# dual_encoder_shield_revB.net
KiCad netlist of a schematic drawn in EAGLE
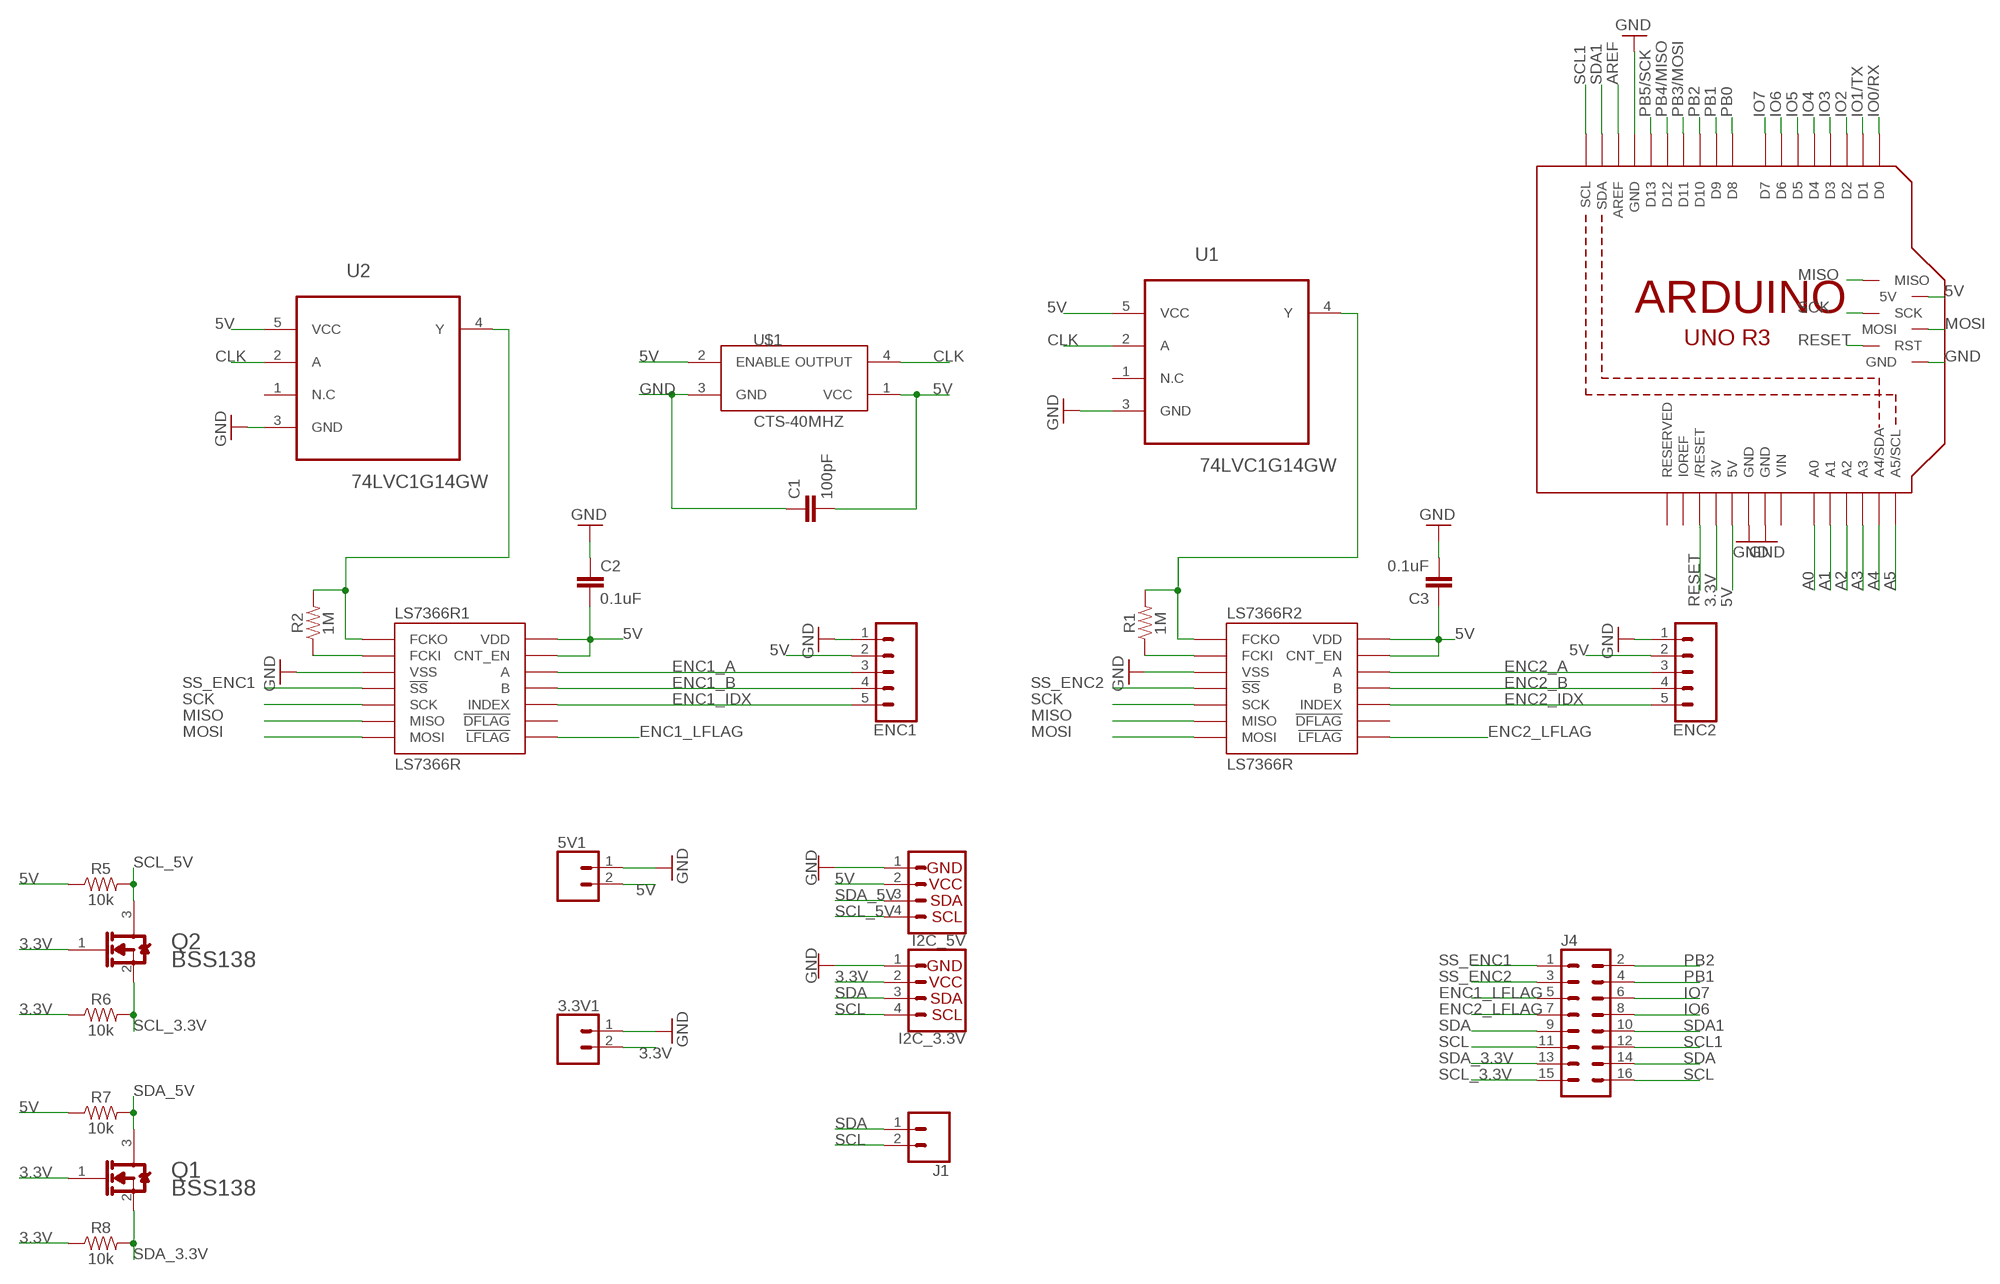
[diagram p0: schematic, sheet 1]

(export (version "E")
  (design (tool "Eeschema 10.0.6"))
  (components
    (comp (ref "3.3V1")
      (value "CONN_02-JST-2MM-SMT")
      (footprint "eagle-import:JST-2-SMD")
      (libsource (lib "eagle-import") (part "CONN_02-JST-2MM-SMT"))
    )
    (comp (ref "5V1")
      (value "CONN_02-JST-2MM-SMT")
      (footprint "eagle-import:JST-2-SMD")
      (libsource (lib "eagle-import") (part "CONN_02-JST-2MM-SMT"))
    )
    (comp (ref "C1")
      (value "100pF")
      (footprint "eagle-import:0603")
      (libsource (lib "eagle-import") (part "100PF-0603-50V-5%"))
    )
    (comp (ref "C2")
      (value "0.1uF")
      (footprint "eagle-import:0603")
      (libsource (lib "eagle-import") (part "0.1UF-0603-25V-5%"))
    )
    (comp (ref "C3")
      (value "0.1uF")
      (footprint "eagle-import:0603")
      (libsource (lib "eagle-import") (part "0.1UF-0603-25V-5%"))
    )
    (comp (ref "ENC1")
      (value "CONN_05")
      (footprint "eagle-import:1X05")
      (libsource (lib "eagle-import") (part "CONN_05"))
    )
    (comp (ref "ENC2")
      (value "CONN_05")
      (footprint "eagle-import:1X05")
      (libsource (lib "eagle-import") (part "CONN_05"))
    )
    (comp (ref "I2C_3.3V")
      (value "QWIIC_CONNECTORJS-1MM")
      (footprint "eagle-import:JST04_1MM_RA")
      (libsource (lib "eagle-import") (part "QWIIC_CONNECTORJS-1MM"))
    )
    (comp (ref "I2C_5V")
      (value "QWIIC_CONNECTORJS-1MM")
      (footprint "eagle-import:JST04_1MM_RA")
      (libsource (lib "eagle-import") (part "QWIIC_CONNECTORJS-1MM"))
    )
    (comp (ref "J1")
      (value "CONN_02")
      (footprint "eagle-import:1X02")
      (libsource (lib "eagle-import") (part "CONN_02"))
    )
    (comp (ref "J4")
      (value "CONN_08X2")
      (footprint "eagle-import:2X8")
      (libsource (lib "eagle-import") (part "CONN_08X2"))
    )
    (comp (ref "LS7366R1")
      (value "LS7366R")
      (footprint "eagle-import:SOIC14")
      (fields (field (name "MF") "LSI"))
      (libsource (lib "eagle-import") (part "LS7366R"))
    )
    (comp (ref "LS7366R2")
      (value "LS7366R")
      (footprint "eagle-import:SOIC14")
      (fields (field (name "MF") "LSI"))
      (libsource (lib "eagle-import") (part "LS7366R"))
    )
    (comp (ref "M1")
      (value "ARDUINO_R3_ICSP")
      (footprint "eagle-import:ARDUINOR3_ICSP")
      (libsource (lib "eagle-import") (part "ARDUINO_R3_ICSP"))
    )
    (comp (ref "Q1")
      (value "ON_SEMI_BSS138ON_SEMI_BSS138_0_0")
      (footprint "eagle-import:ON_SEMI_BSS138_0")
      (fields
        (field (name "DIGIKEY_PART_NUMBER") "BSS138CT-ND")
        (field (name "MF") "ON Semi")
        (field (name "MOUSER_PART_NUMBER") "512-BSS138")
      )
      (libsource (lib "eagle-import") (part "ON_SEMI_BSS138ON_SEMI_BSS138_0_0"))
    )
    (comp (ref "Q2")
      (value "ON_SEMI_BSS138ON_SEMI_BSS138_0_0")
      (footprint "eagle-import:ON_SEMI_BSS138_0")
      (fields
        (field (name "DIGIKEY_PART_NUMBER") "BSS138CT-ND")
        (field (name "MF") "ON Semi")
        (field (name "MOUSER_PART_NUMBER") "512-BSS138")
      )
      (libsource (lib "eagle-import") (part "ON_SEMI_BSS138ON_SEMI_BSS138_0_0"))
    )
    (comp (ref "R1")
      (value "1M")
      (footprint "eagle-import:0603")
      (libsource (lib "eagle-import") (part "1MOHM-0603-1/4W-5%"))
    )
    (comp (ref "R2")
      (value "1M")
      (footprint "eagle-import:0603")
      (libsource (lib "eagle-import") (part "1MOHM-0603-1/4W-5%"))
    )
    (comp (ref "R5")
      (value "10k")
      (footprint "eagle-import:0603")
      (libsource (lib "eagle-import") (part "10KOHM-0603-1/10W-1%"))
    )
    (comp (ref "R6")
      (value "10k")
      (footprint "eagle-import:0603")
      (libsource (lib "eagle-import") (part "10KOHM-0603-1/10W-1%"))
    )
    (comp (ref "R7")
      (value "10k")
      (footprint "eagle-import:0603")
      (libsource (lib "eagle-import") (part "10KOHM-0603-1/10W-1%"))
    )
    (comp (ref "R8")
      (value "10k")
      (footprint "eagle-import:0603")
      (libsource (lib "eagle-import") (part "10KOHM-0603-1/10W-1%"))
    )
    (comp (ref "U$1")
      (value "CTS-40MHZ")
      (footprint "eagle-import:SOIC254P1016X440-4N")
      (libsource (lib "eagle-import") (part "CTS-40MHZ"))
    )
    (comp (ref "U1")
      (value "74LVC1G14GW")
      (footprint "eagle-import:SOT65P210X110-5N")
      (fields (field (name "MF") "NXP Semiconductors"))
      (libsource (lib "eagle-import") (part "74LVC1G14GW"))
    )
    (comp (ref "U2")
      (value "74LVC1G14GW")
      (footprint "eagle-import:SOT65P210X110-5N")
      (fields (field (name "MF") "NXP Semiconductors"))
      (libsource (lib "eagle-import") (part "74LVC1G14GW"))
    )
  )
  (nets
    (net (code "1") (name "/3.3V") (class "Default")
      (node (ref "3.3V1") (pin "2") (pinfunction "1_2") (pintype "passive"))
      (node (ref "I2C_3.3V") (pin "2") (pinfunction "2_2") (pintype "power_in"))
      (node (ref "M1") (pin "3V") (pinfunction "3V_3V") (pintype "power_in"))
      (node (ref "Q1") (pin "1") (pinfunction "G_1") (pintype "bidirectional"))
      (node (ref "Q2") (pin "1") (pinfunction "G_1") (pintype "bidirectional"))
      (node (ref "R6") (pin "1") (pinfunction "1_1") (pintype "passive"))
      (node (ref "R8") (pin "1") (pinfunction "1_1") (pintype "passive"))
    )
    (net (code "2") (name "/5V") (class "Default")
      (node (ref "5V1") (pin "2") (pinfunction "1_2") (pintype "passive"))
      (node (ref "C1") (pin "2") (pinfunction "2_2") (pintype "passive"))
      (node (ref "C2") (pin "2") (pinfunction "2_2") (pintype "passive"))
      (node (ref "C3") (pin "1") (pinfunction "1_1") (pintype "passive"))
      (node (ref "ENC1") (pin "2") (pinfunction "2_2") (pintype "passive"))
      (node (ref "ENC2") (pin "2") (pinfunction "2_2") (pintype "passive"))
      (node (ref "I2C_5V") (pin "2") (pinfunction "2_2") (pintype "power_in"))
      (node (ref "LS7366R1") (pin "13") (pinfunction "CNT_EN_13") (pintype "bidirectional"))
      (node (ref "LS7366R1") (pin "14") (pinfunction "VDD_14") (pintype "bidirectional"))
      (node (ref "LS7366R2") (pin "13") (pinfunction "CNT_EN_13") (pintype "bidirectional"))
      (node (ref "LS7366R2") (pin "14") (pinfunction "VDD_14") (pintype "bidirectional"))
      (node (ref "M1") (pin "5V") (pinfunction "5V_5V") (pintype "power_in"))
      (node (ref "M1") (pin "5V_ICSP") (pinfunction "5V_5V_ICSP") (pintype "passive"))
      (node (ref "R5") (pin "1") (pinfunction "1_1") (pintype "passive"))
      (node (ref "R7") (pin "1") (pinfunction "1_1") (pintype "passive"))
      (node (ref "U$1") (pin "1") (pinfunction "VCC_1") (pintype "bidirectional"))
      (node (ref "U$1") (pin "2") (pinfunction "ENABLE_2") (pintype "bidirectional"))
      (node (ref "U1") (pin "5") (pinfunction "VCC_5") (pintype "power_in"))
      (node (ref "U2") (pin "5") (pinfunction "VCC_5") (pintype "power_in"))
    )
    (net (code "3") (name "/A0") (class "Default")
      (node (ref "M1") (pin "A0") (pinfunction "A0_A0") (pintype "bidirectional"))
    )
    (net (code "4") (name "/A1") (class "Default")
      (node (ref "M1") (pin "A1") (pinfunction "A1_A1") (pintype "bidirectional"))
    )
    (net (code "5") (name "/A2") (class "Default")
      (node (ref "M1") (pin "A2") (pinfunction "A2_A2") (pintype "bidirectional"))
    )
    (net (code "6") (name "/A3") (class "Default")
      (node (ref "M1") (pin "A3") (pinfunction "A3_A3") (pintype "bidirectional"))
    )
    (net (code "7") (name "/A4") (class "Default")
      (node (ref "M1") (pin "A4") (pinfunction "A4/SDA_A4") (pintype "bidirectional"))
    )
    (net (code "8") (name "/A5") (class "Default")
      (node (ref "M1") (pin "A5") (pinfunction "A5/SCL_A5") (pintype "bidirectional"))
    )
    (net (code "9") (name "/AREF") (class "Default")
      (node (ref "M1") (pin "AREF") (pinfunction "AREF_AREF") (pintype "bidirectional"))
    )
    (net (code "10") (name "/CLK") (class "Default")
      (node (ref "U$1") (pin "4") (pinfunction "OUTPUT_4") (pintype "bidirectional"))
      (node (ref "U1") (pin "2") (pinfunction "A_2") (pintype "input"))
      (node (ref "U2") (pin "2") (pinfunction "A_2") (pintype "input"))
    )
    (net (code "11") (name "/ENC1_A") (class "Default")
      (node (ref "ENC1") (pin "3") (pinfunction "3_3") (pintype "passive"))
      (node (ref "LS7366R1") (pin "12") (pinfunction "A_12") (pintype "bidirectional"))
    )
    (net (code "12") (name "/ENC1_B") (class "Default")
      (node (ref "ENC1") (pin "4") (pinfunction "4_4") (pintype "passive"))
      (node (ref "LS7366R1") (pin "11") (pinfunction "B_11") (pintype "bidirectional"))
    )
    (net (code "13") (name "/ENC1_IDX") (class "Default")
      (node (ref "ENC1") (pin "5") (pinfunction "5_5") (pintype "passive"))
      (node (ref "LS7366R1") (pin "10") (pinfunction "INDEX_10") (pintype "bidirectional"))
    )
    (net (code "14") (name "/ENC1_LFLAG") (class "Default")
      (node (ref "J4") (pin "5") (pinfunction "5_5") (pintype "passive"))
      (node (ref "LS7366R1") (pin "8") (pinfunction "~{LFLAG}_8") (pintype "bidirectional"))
    )
    (net (code "15") (name "/ENC2_A") (class "Default")
      (node (ref "ENC2") (pin "3") (pinfunction "3_3") (pintype "passive"))
      (node (ref "LS7366R2") (pin "12") (pinfunction "A_12") (pintype "bidirectional"))
    )
    (net (code "16") (name "/ENC2_B") (class "Default")
      (node (ref "ENC2") (pin "4") (pinfunction "4_4") (pintype "passive"))
      (node (ref "LS7366R2") (pin "11") (pinfunction "B_11") (pintype "bidirectional"))
    )
    (net (code "17") (name "/ENC2_IDX") (class "Default")
      (node (ref "ENC2") (pin "5") (pinfunction "5_5") (pintype "passive"))
      (node (ref "LS7366R2") (pin "10") (pinfunction "INDEX_10") (pintype "bidirectional"))
    )
    (net (code "18") (name "/ENC2_LFLAG") (class "Default")
      (node (ref "J4") (pin "7") (pinfunction "7_7") (pintype "passive"))
      (node (ref "LS7366R2") (pin "8") (pinfunction "~{LFLAG}_8") (pintype "bidirectional"))
    )
    (net (code "19") (name "/IO0{slash}RX") (class "Default")
      (node (ref "M1") (pin "D0") (pinfunction "D0_D0") (pintype "bidirectional"))
    )
    (net (code "20") (name "/IO1{slash}TX") (class "Default")
      (node (ref "M1") (pin "D1") (pinfunction "D1_D1") (pintype "bidirectional"))
    )
    (net (code "21") (name "/IO2") (class "Default")
      (node (ref "M1") (pin "D2") (pinfunction "D2_D2") (pintype "bidirectional"))
    )
    (net (code "22") (name "/IO3") (class "Default")
      (node (ref "M1") (pin "D3") (pinfunction "D3_D3") (pintype "bidirectional"))
    )
    (net (code "23") (name "/IO4") (class "Default")
      (node (ref "M1") (pin "D4") (pinfunction "D4_D4") (pintype "bidirectional"))
    )
    (net (code "24") (name "/IO5") (class "Default")
      (node (ref "M1") (pin "D5") (pinfunction "D5_D5") (pintype "bidirectional"))
    )
    (net (code "25") (name "/IO6") (class "Default")
      (node (ref "J4") (pin "8") (pinfunction "8_8") (pintype "passive"))
      (node (ref "M1") (pin "D6") (pinfunction "D6_D6") (pintype "bidirectional"))
    )
    (net (code "26") (name "/IO7") (class "Default")
      (node (ref "J4") (pin "6") (pinfunction "6_6") (pintype "passive"))
      (node (ref "M1") (pin "D7") (pinfunction "D7_D7") (pintype "bidirectional"))
    )
    (net (code "27") (name "/MISO") (class "Default")
      (node (ref "LS7366R1") (pin "6") (pinfunction "MISO_6") (pintype "bidirectional"))
      (node (ref "LS7366R2") (pin "6") (pinfunction "MISO_6") (pintype "bidirectional"))
      (node (ref "M1") (pin "MISO") (pinfunction "MISO_MISO") (pintype "passive"))
    )
    (net (code "28") (name "/MOSI") (class "Default")
      (node (ref "LS7366R1") (pin "7") (pinfunction "MOSI_7") (pintype "bidirectional"))
      (node (ref "LS7366R2") (pin "7") (pinfunction "MOSI_7") (pintype "bidirectional"))
      (node (ref "M1") (pin "MOSI") (pinfunction "MOSI_MOSI") (pintype "passive"))
    )
    (net (code "29") (name "/PB0") (class "Default")
      (node (ref "M1") (pin "D8") (pinfunction "D8_D8") (pintype "bidirectional"))
    )
    (net (code "30") (name "/PB1") (class "Default")
      (node (ref "J4") (pin "4") (pinfunction "4_4") (pintype "passive"))
      (node (ref "M1") (pin "D9") (pinfunction "D9_D9") (pintype "bidirectional"))
    )
    (net (code "31") (name "/PB2") (class "Default")
      (node (ref "J4") (pin "2") (pinfunction "2_2") (pintype "passive"))
      (node (ref "M1") (pin "D10") (pinfunction "D10_D10") (pintype "bidirectional"))
    )
    (net (code "32") (name "/PB3{slash}MOSI") (class "Default")
      (node (ref "M1") (pin "D11") (pinfunction "D11_D11") (pintype "bidirectional"))
    )
    (net (code "33") (name "/PB4{slash}MISO") (class "Default")
      (node (ref "M1") (pin "D12") (pinfunction "D12_D12") (pintype "bidirectional"))
    )
    (net (code "34") (name "/PB5{slash}SCK") (class "Default")
      (node (ref "M1") (pin "D13") (pinfunction "D13_D13") (pintype "bidirectional"))
    )
    (net (code "35") (name "/RESET") (class "Default")
      (node (ref "M1") (pin "RESET") (pinfunction "/RESET_RESET") (pintype "bidirectional"))
      (node (ref "M1") (pin "RESET_ICSP") (pinfunction "RST_RESET_ICSP") (pintype "passive"))
    )
    (net (code "36") (name "/SCK") (class "Default")
      (node (ref "LS7366R1") (pin "5") (pinfunction "SCK_5") (pintype "bidirectional"))
      (node (ref "LS7366R2") (pin "5") (pinfunction "SCK_5") (pintype "bidirectional"))
      (node (ref "M1") (pin "SCK") (pinfunction "SCK_SCK") (pintype "passive"))
    )
    (net (code "37") (name "/SCL") (class "Default")
      (node (ref "I2C_3.3V") (pin "4") (pinfunction "4_4") (pintype "passive"))
      (node (ref "J1") (pin "2") (pinfunction "2_2") (pintype "passive"))
      (node (ref "J4") (pin "11") (pinfunction "11_11") (pintype "passive"))
      (node (ref "J4") (pin "16") (pinfunction "16_16") (pintype "passive"))
    )
    (net (code "38") (name "/SCL1") (class "Default")
      (node (ref "J4") (pin "12") (pinfunction "12_12") (pintype "passive"))
      (node (ref "M1") (pin "SCL") (pinfunction "SCL_SCL") (pintype "bidirectional"))
    )
    (net (code "39") (name "/SCL_3.3V") (class "Default")
      (node (ref "J4") (pin "15") (pinfunction "15_15") (pintype "passive"))
      (node (ref "Q2") (pin "2") (pinfunction "S_2") (pintype "bidirectional"))
      (node (ref "R6") (pin "2") (pinfunction "2_2") (pintype "passive"))
    )
    (net (code "40") (name "/SCL_5V") (class "Default")
      (node (ref "I2C_5V") (pin "4") (pinfunction "4_4") (pintype "passive"))
      (node (ref "Q2") (pin "3") (pinfunction "D_3") (pintype "bidirectional"))
      (node (ref "R5") (pin "2") (pinfunction "2_2") (pintype "passive"))
    )
    (net (code "41") (name "/SDA") (class "Default")
      (node (ref "I2C_3.3V") (pin "3") (pinfunction "3_3") (pintype "passive"))
      (node (ref "J1") (pin "1") (pinfunction "1_1") (pintype "passive"))
      (node (ref "J4") (pin "14") (pinfunction "14_14") (pintype "passive"))
      (node (ref "J4") (pin "9") (pinfunction "9_9") (pintype "passive"))
    )
    (net (code "42") (name "/SDA1") (class "Default")
      (node (ref "J4") (pin "10") (pinfunction "10_10") (pintype "passive"))
      (node (ref "M1") (pin "SDA") (pinfunction "SDA_SDA") (pintype "bidirectional"))
    )
    (net (code "43") (name "/SDA_3.3V") (class "Default")
      (node (ref "J4") (pin "13") (pinfunction "13_13") (pintype "passive"))
      (node (ref "Q1") (pin "2") (pinfunction "S_2") (pintype "bidirectional"))
      (node (ref "R8") (pin "2") (pinfunction "2_2") (pintype "passive"))
    )
    (net (code "44") (name "/SDA_5V") (class "Default")
      (node (ref "I2C_5V") (pin "3") (pinfunction "3_3") (pintype "passive"))
      (node (ref "Q1") (pin "3") (pinfunction "D_3") (pintype "bidirectional"))
      (node (ref "R7") (pin "2") (pinfunction "2_2") (pintype "passive"))
    )
    (net (code "45") (name "/SS_ENC1") (class "Default")
      (node (ref "J4") (pin "1") (pinfunction "1_1") (pintype "passive"))
      (node (ref "LS7366R1") (pin "4") (pinfunction "~{SS}_4") (pintype "bidirectional"))
    )
    (net (code "46") (name "/SS_ENC2") (class "Default")
      (node (ref "J4") (pin "3") (pinfunction "3_3") (pintype "passive"))
      (node (ref "LS7366R2") (pin "4") (pinfunction "~{SS}_4") (pintype "bidirectional"))
    )
    (net (code "47") (name "/VIN") (class "Default")
      (node (ref "M1") (pin "VIN") (pinfunction "VIN_VIN") (pintype "power_in"))
    )
    (net (code "48") (name "GND") (class "Default")
      (node (ref "3.3V1") (pin "1") (pinfunction "2_1") (pintype "passive"))
      (node (ref "5V1") (pin "1") (pinfunction "2_1") (pintype "passive"))
      (node (ref "C1") (pin "1") (pinfunction "1_1") (pintype "passive"))
      (node (ref "C2") (pin "1") (pinfunction "1_1") (pintype "passive"))
      (node (ref "C3") (pin "2") (pinfunction "2_2") (pintype "passive"))
      (node (ref "ENC1") (pin "1") (pinfunction "1_1") (pintype "passive"))
      (node (ref "ENC2") (pin "1") (pinfunction "1_1") (pintype "passive"))
      (node (ref "I2C_3.3V") (pin "1") (pinfunction "1_1") (pintype "power_in"))
      (node (ref "I2C_5V") (pin "1") (pinfunction "1_1") (pintype "power_in"))
      (node (ref "LS7366R1") (pin "3") (pinfunction "VSS_3") (pintype "bidirectional"))
      (node (ref "LS7366R2") (pin "3") (pinfunction "VSS_3") (pintype "bidirectional"))
      (node (ref "M1") (pin "GND") (pinfunction "GND_GND") (pintype "power_in"))
      (node (ref "M1") (pin "GND@1") (pinfunction "GND_GND@1") (pintype "power_in"))
      (node (ref "M1") (pin "GND@2") (pinfunction "GND_GND@2") (pintype "passive"))
      (node (ref "M1") (pin "GND@3") (pinfunction "GND_GND@3") (pintype "power_in"))
      (node (ref "U$1") (pin "3") (pinfunction "GND_3") (pintype "bidirectional"))
      (node (ref "U1") (pin "3") (pinfunction "GND_3") (pintype "passive"))
      (node (ref "U2") (pin "3") (pinfunction "GND_3") (pintype "passive"))
    )
    (net (code "49") (name "Net-(LS7366R1-FCKI)") (class "Default")
      (node (ref "LS7366R1") (pin "2") (pinfunction "FCKI_2") (pintype "bidirectional"))
      (node (ref "R2") (pin "1") (pinfunction "1_1") (pintype "passive"))
    )
    (net (code "50") (name "Net-(LS7366R1-FCKO)") (class "Default")
      (node (ref "LS7366R1") (pin "1") (pinfunction "FCKO_1") (pintype "bidirectional"))
      (node (ref "R2") (pin "2") (pinfunction "2_2") (pintype "passive"))
      (node (ref "U2") (pin "4") (pinfunction "Y_4") (pintype "output"))
    )
    (net (code "51") (name "Net-(LS7366R2-FCKI)") (class "Default")
      (node (ref "LS7366R2") (pin "2") (pinfunction "FCKI_2") (pintype "bidirectional"))
      (node (ref "R1") (pin "1") (pinfunction "1_1") (pintype "passive"))
    )
    (net (code "52") (name "Net-(LS7366R2-FCKO)") (class "Default")
      (node (ref "LS7366R2") (pin "1") (pinfunction "FCKO_1") (pintype "bidirectional"))
      (node (ref "R1") (pin "2") (pinfunction "2_2") (pintype "passive"))
      (node (ref "U1") (pin "4") (pinfunction "Y_4") (pintype "output"))
    )
    (net (code "53") (name "unconnected-(LS7366R1-~{DFLAG}-Pad9)") (class "Default")
      (node (ref "LS7366R1") (pin "9") (pinfunction "~{DFLAG}_9") (pintype "bidirectional"))
    )
    (net (code "54") (name "unconnected-(LS7366R2-~{DFLAG}-Pad9)") (class "Default")
      (node (ref "LS7366R2") (pin "9") (pinfunction "~{DFLAG}_9") (pintype "bidirectional"))
    )
    (net (code "55") (name "unconnected-(M1-PadIOREF)") (class "Default")
      (node (ref "M1") (pin "IOREF") (pinfunction "IOREF_IOREF") (pintype "output"))
    )
    (net (code "56") (name "unconnected-(M1-PadRESERVED)") (class "Default")
      (node (ref "M1") (pin "RESERVED") (pinfunction "RESERVED_RESERVED") (pintype "no_connect"))
    )
    (net (code "57") (name "unconnected-(U1-N.C-Pad1)") (class "Default")
      (node (ref "U1") (pin "1") (pinfunction "N.C_1") (pintype "no_connect"))
    )
    (net (code "58") (name "unconnected-(U2-N.C-Pad1)") (class "Default")
      (node (ref "U2") (pin "1") (pinfunction "N.C_1") (pintype "no_connect"))
    )
  )
)
